# Rev_1.net
KiCad netlist of a schematic drawn in EAGLE
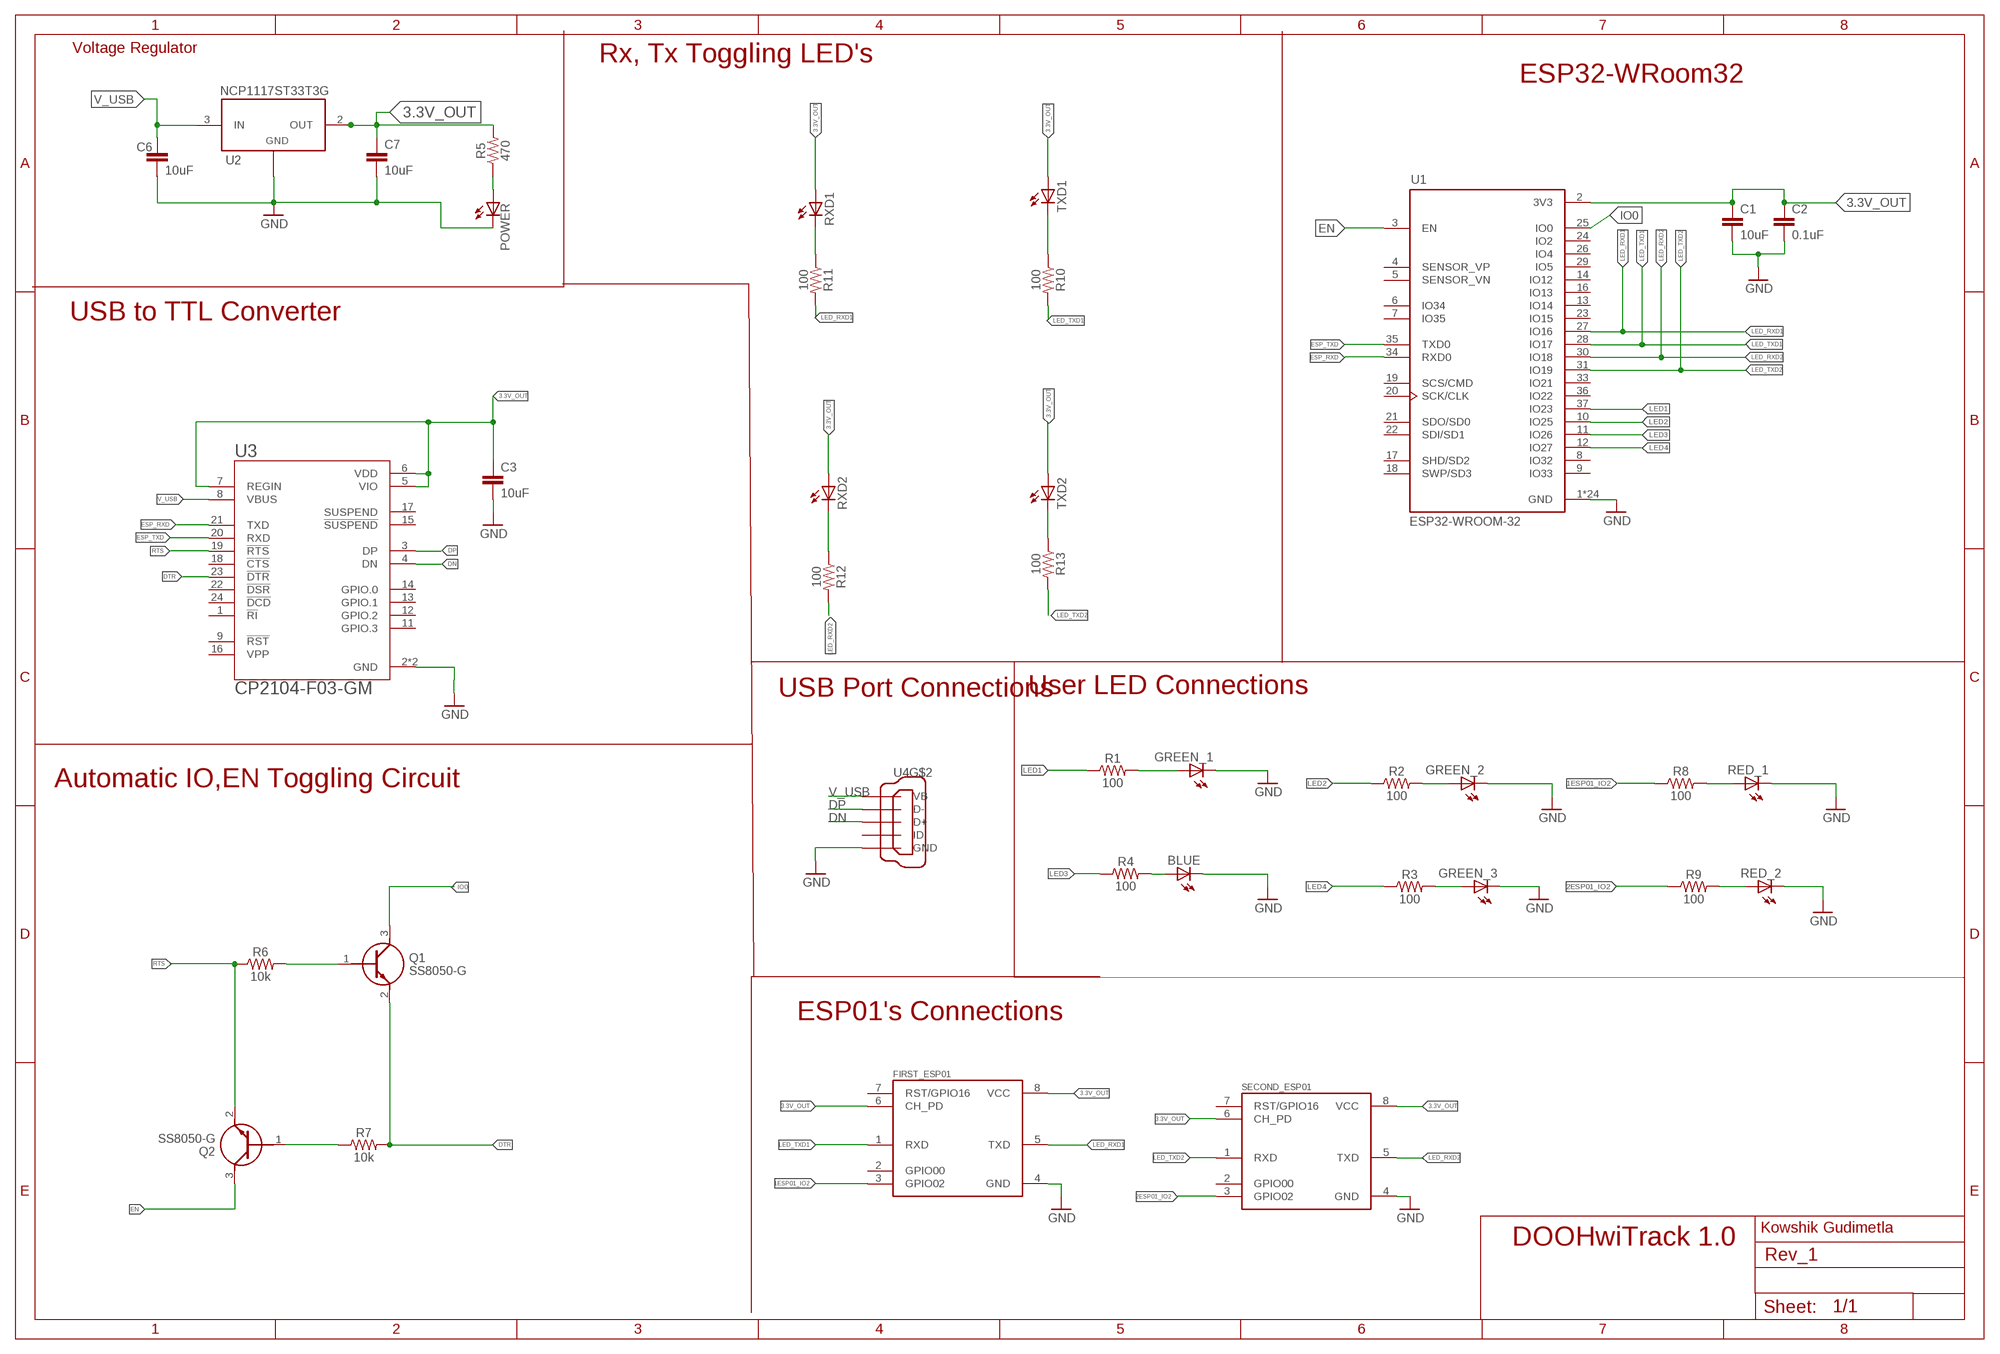
[diagram p0: schematic, sheet 1]

(export (version "E")
  (design (tool "Eeschema 10.0.6"))
  (components
    (comp (ref "BLUE")
      (value "LEDCHIP-LED0805")
      (footprint "eagle-import:CHIP-LED0805")
      (libsource (lib "eagle-import") (part "LEDCHIP-LED0805"))
    )
    (comp (ref "C1")
      (value "10uF")
      (footprint "eagle-import:0402")
      (libsource (lib "eagle-import") (part "0.1UF-0402-16V-10%"))
    )
    (comp (ref "C2")
      (value "0.1uF")
      (footprint "eagle-import:0402")
      (libsource (lib "eagle-import") (part "0.1UF-0402-16V-10%"))
    )
    (comp (ref "C3")
      (value "10uF")
      (footprint "eagle-import:0402")
      (libsource (lib "eagle-import") (part "0.1UF-0402-16V-10%"))
    )
    (comp (ref "C6")
      (value "10uF")
      (footprint "eagle-import:0402")
      (libsource (lib "eagle-import") (part "0.1UF-0402-16V-10%"))
    )
    (comp (ref "C7")
      (value "10uF")
      (footprint "eagle-import:0402")
      (libsource (lib "eagle-import") (part "0.1UF-0402-16V-10%"))
    )
    (comp (ref "FIRST_ESP01")
      (value "ESP8266-01/ESP-01")
      (footprint "eagle-import:XCVR_ESP8266-01_ESP-01")
      (fields (field (name "MF") "AI-Thinker"))
      (libsource (lib "eagle-import") (part "ESP8266-01/ESP-01"))
    )
    (comp (ref "GREEN_1")
      (value "LEDCHIP-LED0805")
      (footprint "eagle-import:CHIP-LED0805")
      (libsource (lib "eagle-import") (part "LEDCHIP-LED0805"))
    )
    (comp (ref "GREEN_2")
      (value "LEDCHIP-LED0805")
      (footprint "eagle-import:CHIP-LED0805")
      (libsource (lib "eagle-import") (part "LEDCHIP-LED0805"))
    )
    (comp (ref "GREEN_3")
      (value "LEDCHIP-LED0805")
      (footprint "eagle-import:CHIP-LED0805")
      (libsource (lib "eagle-import") (part "LEDCHIP-LED0805"))
    )
    (comp (ref "POWER")
      (value "LEDCHIP-LED0603")
      (footprint "eagle-import:CHIP-LED0603")
      (libsource (lib "eagle-import") (part "LEDCHIP-LED0603"))
    )
    (comp (ref "Q1")
      (value "SS8050-G")
      (footprint "eagle-import:SOT95P240X115-3N")
      (fields (field (name "MF") "Comchip Technology"))
      (libsource (lib "eagle-import") (part "SS8050-G"))
    )
    (comp (ref "Q2")
      (value "SS8050-G")
      (footprint "eagle-import:SOT95P240X115-3N")
      (fields (field (name "MF") "Comchip Technology"))
      (libsource (lib "eagle-import") (part "SS8050-G"))
    )
    (comp (ref "R1")
      (value "100")
      (footprint "eagle-import:0402")
      (libsource (lib "eagle-import") (part "100KOHM-0402-1/16W-1%"))
    )
    (comp (ref "R2")
      (value "100")
      (footprint "eagle-import:0402")
      (libsource (lib "eagle-import") (part "100KOHM-0402-1/16W-1%"))
    )
    (comp (ref "R3")
      (value "100")
      (footprint "eagle-import:0402")
      (libsource (lib "eagle-import") (part "100KOHM-0402-1/16W-1%"))
    )
    (comp (ref "R4")
      (value "100")
      (footprint "eagle-import:0402")
      (libsource (lib "eagle-import") (part "100KOHM-0402-1/16W-1%"))
    )
    (comp (ref "R5")
      (value "470")
      (footprint "eagle-import:0402")
      (libsource (lib "eagle-import") (part "100KOHM-0402-1/16W-1%"))
    )
    (comp (ref "R6")
      (value "10k")
      (footprint "eagle-import:0402")
      (libsource (lib "eagle-import") (part "100KOHM-0402-1/16W-1%"))
    )
    (comp (ref "R7")
      (value "10k")
      (footprint "eagle-import:0402")
      (libsource (lib "eagle-import") (part "100KOHM-0402-1/16W-1%"))
    )
    (comp (ref "R8")
      (value "100")
      (footprint "eagle-import:0402")
      (libsource (lib "eagle-import") (part "100KOHM-0402-1/16W-1%"))
    )
    (comp (ref "R9")
      (value "100")
      (footprint "eagle-import:0402")
      (libsource (lib "eagle-import") (part "100KOHM-0402-1/16W-1%"))
    )
    (comp (ref "R10")
      (value "100")
      (footprint "eagle-import:0402")
      (libsource (lib "eagle-import") (part "100KOHM-0402-1/16W-1%"))
    )
    (comp (ref "R11")
      (value "100")
      (footprint "eagle-import:0402")
      (libsource (lib "eagle-import") (part "100KOHM-0402-1/16W-1%"))
    )
    (comp (ref "R12")
      (value "100")
      (footprint "eagle-import:0402")
      (libsource (lib "eagle-import") (part "100KOHM-0402-1/16W-1%"))
    )
    (comp (ref "R13")
      (value "100")
      (footprint "eagle-import:0402")
      (libsource (lib "eagle-import") (part "100KOHM-0402-1/16W-1%"))
    )
    (comp (ref "RED_1")
      (value "LEDCHIP-LED0805")
      (footprint "eagle-import:CHIP-LED0805")
      (libsource (lib "eagle-import") (part "LEDCHIP-LED0805"))
    )
    (comp (ref "RED_2")
      (value "LEDCHIP-LED0805")
      (footprint "eagle-import:CHIP-LED0805")
      (libsource (lib "eagle-import") (part "LEDCHIP-LED0805"))
    )
    (comp (ref "RXD1")
      (value "LEDCHIP-LED0805")
      (footprint "eagle-import:CHIP-LED0805")
      (libsource (lib "eagle-import") (part "LEDCHIP-LED0805"))
    )
    (comp (ref "RXD2")
      (value "LEDCHIP-LED0805")
      (footprint "eagle-import:CHIP-LED0805")
      (libsource (lib "eagle-import") (part "LEDCHIP-LED0805"))
    )
    (comp (ref "SECOND_ESP01")
      (value "ESP8266-01/ESP-01")
      (footprint "eagle-import:XCVR_ESP8266-01_ESP-01")
      (fields (field (name "MF") "AI-Thinker"))
      (libsource (lib "eagle-import") (part "ESP8266-01/ESP-01"))
    )
    (comp (ref "TXD1")
      (value "LEDCHIP-LED0805")
      (footprint "eagle-import:CHIP-LED0805")
      (libsource (lib "eagle-import") (part "LEDCHIP-LED0805"))
    )
    (comp (ref "TXD2")
      (value "LEDCHIP-LED0805")
      (footprint "eagle-import:CHIP-LED0805")
      (libsource (lib "eagle-import") (part "LEDCHIP-LED0805"))
    )
    (comp (ref "U1")
      (value "ESP32-WROOM-32")
      (footprint "eagle-import:MODULE_ESP32-WROOM-32")
      (fields (field (name "MF") "Espressif Systems"))
      (libsource (lib "eagle-import") (part "ESP32-WROOM-32"))
    )
    (comp (ref "U2")
      (value "NCP1117ST33T3G")
      (footprint "eagle-import:SOT-223")
      (fields
        (field (name "DIGIKEY_PART_NUMBER") "NCP1117ST33T3GOSTR-ND")
        (field (name "MANUFACTURER") "ON Semiconductor")
        (field (name "CREATED_BY") "PCBLayout.com")
      )
      (libsource (lib "eagle-import") (part "NCP1117ST33T3G"))
    )
    (comp (ref "U3")
      (value "CP2104-F03-GM")
      (footprint "eagle-import:QFN50P400X400X80-25N")
      (fields (field (name "MF") "Silicon Labs") (field (name "MP") "CP2104"))
      (libsource (lib "eagle-import") (part "CP2104-F03-GM"))
    )
    (comp (ref "U4")
      (value "J_USB_MICROAB_HIROSE_ZX62-AB-5PA")
      (footprint "eagle-import:J_USB_MICROAB_HIROSE_ZX62-AB-5PA")
      (libsource (lib "eagle-import") (part "J_USB_MICROAB_HIROSE_ZX62-AB-5PA"))
    )
  )
  (nets
    (net (code "1") (name "1ESP01_IO2") (class "Default")
      (node (ref "FIRST_ESP01") (pin "3") (pinfunction "GPIO02_3") (pintype "bidirectional"))
      (node (ref "R8") (pin "1") (pinfunction "1_1") (pintype "passive"))
    )
    (net (code "2") (name "2ESP01_IO2") (class "Default")
      (node (ref "R9") (pin "1") (pinfunction "1_1") (pintype "passive"))
      (node (ref "SECOND_ESP01") (pin "3") (pinfunction "GPIO02_3") (pintype "bidirectional"))
    )
    (net (code "3") (name "3.3V_OUT") (class "Default")
      (node (ref "C1") (pin "1") (pinfunction "1_1") (pintype "passive"))
      (node (ref "C2") (pin "1") (pinfunction "1_1") (pintype "passive"))
      (node (ref "C3") (pin "1") (pinfunction "1_1") (pintype "passive"))
      (node (ref "C7") (pin "1") (pinfunction "1_1") (pintype "passive"))
      (node (ref "FIRST_ESP01") (pin "6") (pinfunction "CH_PD_6") (pintype "input"))
      (node (ref "FIRST_ESP01") (pin "8") (pinfunction "VCC_8") (pintype "power_in"))
      (node (ref "R5") (pin "2") (pinfunction "2_2") (pintype "passive"))
      (node (ref "RXD1") (pin "A") (pinfunction "A_A") (pintype "passive"))
      (node (ref "RXD2") (pin "A") (pinfunction "A_A") (pintype "passive"))
      (node (ref "SECOND_ESP01") (pin "6") (pinfunction "CH_PD_6") (pintype "input"))
      (node (ref "SECOND_ESP01") (pin "8") (pinfunction "VCC_8") (pintype "power_in"))
      (node (ref "TXD1") (pin "A") (pinfunction "A_A") (pintype "passive"))
      (node (ref "TXD2") (pin "A") (pinfunction "A_A") (pintype "passive"))
      (node (ref "U1") (pin "2") (pinfunction "3V3_2") (pintype "power_in"))
      (node (ref "U2") (pin "2") (pinfunction "OUT_2") (pintype "output"))
      (node (ref "U2") (pin "4") (pinfunction "4_4") (pintype "passive"))
      (node (ref "U3") (pin "5") (pinfunction "VIO_5") (pintype "power_in"))
      (node (ref "U3") (pin "6") (pinfunction "VDD_6") (pintype "power_in"))
      (node (ref "U3") (pin "7") (pinfunction "REGIN_7") (pintype "input"))
    )
    (net (code "4") (name "DN") (class "Default")
      (node (ref "U3") (pin "4") (pinfunction "DN_4") (pintype "bidirectional"))
      (node (ref "U4") (pin "P$3") (pinfunction "D+_P$3") (pintype "passive"))
    )
    (net (code "5") (name "DP") (class "Default")
      (node (ref "U3") (pin "3") (pinfunction "DP_3") (pintype "bidirectional"))
      (node (ref "U4") (pin "P$2") (pinfunction "D-_P$2") (pintype "passive"))
    )
    (net (code "6") (name "DTR") (class "Default")
      (node (ref "Q1") (pin "2") (pinfunction "E_2") (pintype "bidirectional"))
      (node (ref "R7") (pin "2") (pinfunction "2_2") (pintype "passive"))
      (node (ref "U3") (pin "23") (pinfunction "~{DTR}_23") (pintype "output"))
    )
    (net (code "7") (name "EN") (class "Default")
      (node (ref "Q2") (pin "3") (pinfunction "C_3") (pintype "bidirectional"))
      (node (ref "U1") (pin "3") (pinfunction "EN_3") (pintype "input"))
    )
    (net (code "8") (name "ESP_RXD") (class "Default")
      (node (ref "U1") (pin "34") (pinfunction "RXD0_34") (pintype "bidirectional"))
      (node (ref "U3") (pin "21") (pinfunction "TXD_21") (pintype "output"))
    )
    (net (code "9") (name "ESP_TXD") (class "Default")
      (node (ref "U1") (pin "35") (pinfunction "TXD0_35") (pintype "bidirectional"))
      (node (ref "U3") (pin "20") (pinfunction "RXD_20") (pintype "input"))
    )
    (net (code "10") (name "GND") (class "Default")
      (node (ref "BLUE") (pin "C") (pinfunction "C_C") (pintype "passive"))
      (node (ref "C1") (pin "2") (pinfunction "2_2") (pintype "passive"))
      (node (ref "C2") (pin "2") (pinfunction "2_2") (pintype "passive"))
      (node (ref "C3") (pin "2") (pinfunction "2_2") (pintype "passive"))
      (node (ref "C6") (pin "2") (pinfunction "2_2") (pintype "passive"))
      (node (ref "C7") (pin "2") (pinfunction "2_2") (pintype "passive"))
      (node (ref "FIRST_ESP01") (pin "4") (pinfunction "GND_4") (pintype "power_in"))
      (node (ref "GREEN_1") (pin "C") (pinfunction "C_C") (pintype "passive"))
      (node (ref "GREEN_2") (pin "C") (pinfunction "C_C") (pintype "passive"))
      (node (ref "GREEN_3") (pin "C") (pinfunction "C_C") (pintype "passive"))
      (node (ref "POWER") (pin "C") (pinfunction "C_C") (pintype "passive"))
      (node (ref "RED_1") (pin "C") (pinfunction "C_C") (pintype "passive"))
      (node (ref "RED_2") (pin "C") (pinfunction "C_C") (pintype "passive"))
      (node (ref "SECOND_ESP01") (pin "4") (pinfunction "GND_4") (pintype "power_in"))
      (node (ref "U1") (pin "1") (pinfunction "GND_1") (pintype "power_in"))
      (node (ref "U1") (pin "15") (pinfunction "GND_15") (pintype "power_in"))
      (node (ref "U1") (pin "38") (pinfunction "GND_38") (pintype "power_in"))
      (node (ref "U1") (pin "39_1") (pinfunction "GND_39_1") (pintype "power_in"))
      (node (ref "U1") (pin "39_10") (pinfunction "GND_39_10") (pintype "power_in"))
      (node (ref "U1") (pin "39_11") (pinfunction "GND_39_11") (pintype "power_in"))
      (node (ref "U1") (pin "39_12") (pinfunction "GND_39_12") (pintype "power_in"))
      (node (ref "U1") (pin "39_13") (pinfunction "GND_39_13") (pintype "power_in"))
      (node (ref "U1") (pin "39_14") (pinfunction "GND_39_14") (pintype "power_in"))
      (node (ref "U1") (pin "39_15") (pinfunction "GND_39_15") (pintype "power_in"))
      (node (ref "U1") (pin "39_16") (pinfunction "GND_39_16") (pintype "power_in"))
      (node (ref "U1") (pin "39_17") (pinfunction "GND_39_17") (pintype "power_in"))
      (node (ref "U1") (pin "39_18") (pinfunction "GND_39_18") (pintype "power_in"))
      (node (ref "U1") (pin "39_19") (pinfunction "GND_39_19") (pintype "power_in"))
      (node (ref "U1") (pin "39_2") (pinfunction "GND_39_2") (pintype "power_in"))
      (node (ref "U1") (pin "39_20") (pinfunction "GND_39_20") (pintype "power_in"))
      (node (ref "U1") (pin "39_21") (pinfunction "GND_39_21") (pintype "power_in"))
      (node (ref "U1") (pin "39_3") (pinfunction "GND_39_3") (pintype "power_in"))
      (node (ref "U1") (pin "39_4") (pinfunction "GND_39_4") (pintype "power_in"))
      (node (ref "U1") (pin "39_5") (pinfunction "GND_39_5") (pintype "power_in"))
      (node (ref "U1") (pin "39_6") (pinfunction "GND_39_6") (pintype "power_in"))
      (node (ref "U1") (pin "39_7") (pinfunction "GND_39_7") (pintype "power_in"))
      (node (ref "U1") (pin "39_8") (pinfunction "GND_39_8") (pintype "power_in"))
      (node (ref "U1") (pin "39_9") (pinfunction "GND_39_9") (pintype "power_in"))
      (node (ref "U2") (pin "1") (pinfunction "ADJ/GND_1") (pintype "power_in"))
      (node (ref "U3") (pin "2") (pinfunction "GND_2") (pintype "power_in"))
      (node (ref "U3") (pin "25") (pinfunction "GND_25") (pintype "power_in"))
      (node (ref "U4") (pin "P$5") (pinfunction "GND_P$5") (pintype "passive"))
    )
    (net (code "11") (name "IO0") (class "Default")
      (node (ref "Q1") (pin "3") (pinfunction "C_3") (pintype "bidirectional"))
      (node (ref "U1") (pin "25") (pinfunction "IO0_25") (pintype "bidirectional"))
    )
    (net (code "12") (name "LED1") (class "Default")
      (node (ref "R1") (pin "1") (pinfunction "1_1") (pintype "passive"))
      (node (ref "U1") (pin "37") (pinfunction "IO23_37") (pintype "bidirectional"))
    )
    (net (code "13") (name "LED2") (class "Default")
      (node (ref "R2") (pin "1") (pinfunction "1_1") (pintype "passive"))
      (node (ref "U1") (pin "10") (pinfunction "IO25_10") (pintype "bidirectional"))
    )
    (net (code "14") (name "LED3") (class "Default")
      (node (ref "R4") (pin "1") (pinfunction "1_1") (pintype "passive"))
      (node (ref "U1") (pin "11") (pinfunction "IO26_11") (pintype "bidirectional"))
    )
    (net (code "15") (name "LED4") (class "Default")
      (node (ref "R3") (pin "1") (pinfunction "1_1") (pintype "passive"))
      (node (ref "U1") (pin "12") (pinfunction "IO27_12") (pintype "bidirectional"))
    )
    (net (code "16") (name "LED_RXD1") (class "Default")
      (node (ref "FIRST_ESP01") (pin "5") (pinfunction "TXD_5") (pintype "output"))
      (node (ref "R11") (pin "2") (pinfunction "2_2") (pintype "passive"))
      (node (ref "U1") (pin "27") (pinfunction "IO16_27") (pintype "bidirectional"))
    )
    (net (code "17") (name "LED_RXD2") (class "Default")
      (node (ref "R12") (pin "2") (pinfunction "2_2") (pintype "passive"))
      (node (ref "SECOND_ESP01") (pin "5") (pinfunction "TXD_5") (pintype "output"))
      (node (ref "U1") (pin "30") (pinfunction "IO18_30") (pintype "bidirectional"))
    )
    (net (code "18") (name "LED_TXD1") (class "Default")
      (node (ref "FIRST_ESP01") (pin "1") (pinfunction "RXD_1") (pintype "input"))
      (node (ref "R10") (pin "2") (pinfunction "2_2") (pintype "passive"))
      (node (ref "U1") (pin "28") (pinfunction "IO17_28") (pintype "bidirectional"))
    )
    (net (code "19") (name "LED_TXD2") (class "Default")
      (node (ref "R13") (pin "2") (pinfunction "2_2") (pintype "passive"))
      (node (ref "SECOND_ESP01") (pin "1") (pinfunction "RXD_1") (pintype "input"))
      (node (ref "U1") (pin "31") (pinfunction "IO19_31") (pintype "bidirectional"))
    )
    (net (code "20") (name "Net-(BLUE-PadA)") (class "Default")
      (node (ref "BLUE") (pin "A") (pinfunction "A_A") (pintype "passive"))
      (node (ref "R4") (pin "2") (pinfunction "2_2") (pintype "passive"))
    )
    (net (code "21") (name "Net-(GREEN_1-PadA)") (class "Default")
      (node (ref "GREEN_1") (pin "A") (pinfunction "A_A") (pintype "passive"))
      (node (ref "R1") (pin "2") (pinfunction "2_2") (pintype "passive"))
    )
    (net (code "22") (name "Net-(GREEN_2-PadA)") (class "Default")
      (node (ref "GREEN_2") (pin "A") (pinfunction "A_A") (pintype "passive"))
      (node (ref "R2") (pin "2") (pinfunction "2_2") (pintype "passive"))
    )
    (net (code "23") (name "Net-(GREEN_3-PadA)") (class "Default")
      (node (ref "GREEN_3") (pin "A") (pinfunction "A_A") (pintype "passive"))
      (node (ref "R3") (pin "2") (pinfunction "2_2") (pintype "passive"))
    )
    (net (code "24") (name "Net-(POWER-PadA)") (class "Default")
      (node (ref "POWER") (pin "A") (pinfunction "A_A") (pintype "passive"))
      (node (ref "R5") (pin "1") (pinfunction "1_1") (pintype "passive"))
    )
    (net (code "25") (name "Net-(Q1-B)") (class "Default")
      (node (ref "Q1") (pin "1") (pinfunction "B_1") (pintype "bidirectional"))
      (node (ref "R6") (pin "2") (pinfunction "2_2") (pintype "passive"))
    )
    (net (code "26") (name "Net-(Q2-B)") (class "Default")
      (node (ref "Q2") (pin "1") (pinfunction "B_1") (pintype "bidirectional"))
      (node (ref "R7") (pin "1") (pinfunction "1_1") (pintype "passive"))
    )
    (net (code "27") (name "Net-(R8-Pad2)") (class "Default")
      (node (ref "R8") (pin "2") (pinfunction "2_2") (pintype "passive"))
      (node (ref "RED_1") (pin "A") (pinfunction "A_A") (pintype "passive"))
    )
    (net (code "28") (name "Net-(R9-Pad2)") (class "Default")
      (node (ref "R9") (pin "2") (pinfunction "2_2") (pintype "passive"))
      (node (ref "RED_2") (pin "A") (pinfunction "A_A") (pintype "passive"))
    )
    (net (code "29") (name "Net-(R10-Pad1)") (class "Default")
      (node (ref "R10") (pin "1") (pinfunction "1_1") (pintype "passive"))
      (node (ref "TXD1") (pin "C") (pinfunction "C_C") (pintype "passive"))
    )
    (net (code "30") (name "Net-(R11-Pad1)") (class "Default")
      (node (ref "R11") (pin "1") (pinfunction "1_1") (pintype "passive"))
      (node (ref "RXD1") (pin "C") (pinfunction "C_C") (pintype "passive"))
    )
    (net (code "31") (name "Net-(R12-Pad1)") (class "Default")
      (node (ref "R12") (pin "1") (pinfunction "1_1") (pintype "passive"))
      (node (ref "RXD2") (pin "C") (pinfunction "C_C") (pintype "passive"))
    )
    (net (code "32") (name "Net-(R13-Pad1)") (class "Default")
      (node (ref "R13") (pin "1") (pinfunction "1_1") (pintype "passive"))
      (node (ref "TXD2") (pin "C") (pinfunction "C_C") (pintype "passive"))
    )
    (net (code "33") (name "RTS") (class "Default")
      (node (ref "Q2") (pin "2") (pinfunction "E_2") (pintype "bidirectional"))
      (node (ref "R6") (pin "1") (pinfunction "1_1") (pintype "passive"))
      (node (ref "U3") (pin "19") (pinfunction "~{RTS}_19") (pintype "output"))
    )
    (net (code "34") (name "V_USB") (class "Default")
      (node (ref "C6") (pin "1") (pinfunction "1_1") (pintype "passive"))
      (node (ref "U2") (pin "3") (pinfunction "IN_3") (pintype "input"))
      (node (ref "U3") (pin "8") (pinfunction "VBUS_8") (pintype "input"))
      (node (ref "U4") (pin "P$1") (pinfunction "VB_P$1") (pintype "passive"))
    )
    (net (code "35") (name "unconnected-(FIRST_ESP01-GPIO00-Pad2)") (class "Default")
      (node (ref "FIRST_ESP01") (pin "2") (pinfunction "GPIO00_2") (pintype "bidirectional"))
    )
    (net (code "36") (name "unconnected-(FIRST_ESP01-RST{slash}GPIO16-Pad7)") (class "Default")
      (node (ref "FIRST_ESP01") (pin "7") (pinfunction "RST/GPIO16_7") (pintype "input"))
    )
    (net (code "37") (name "unconnected-(SECOND_ESP01-GPIO00-Pad2)") (class "Default")
      (node (ref "SECOND_ESP01") (pin "2") (pinfunction "GPIO00_2") (pintype "bidirectional"))
    )
    (net (code "38") (name "unconnected-(SECOND_ESP01-RST{slash}GPIO16-Pad7)") (class "Default")
      (node (ref "SECOND_ESP01") (pin "7") (pinfunction "RST/GPIO16_7") (pintype "input"))
    )
    (net (code "39") (name "unconnected-(U1-IO2-Pad24)") (class "Default")
      (node (ref "U1") (pin "24") (pinfunction "IO2_24") (pintype "bidirectional"))
    )
    (net (code "40") (name "unconnected-(U1-IO4-Pad26)") (class "Default")
      (node (ref "U1") (pin "26") (pinfunction "IO4_26") (pintype "bidirectional"))
    )
    (net (code "41") (name "unconnected-(U1-IO5-Pad29)") (class "Default")
      (node (ref "U1") (pin "29") (pinfunction "IO5_29") (pintype "bidirectional"))
    )
    (net (code "42") (name "unconnected-(U1-IO12-Pad14)") (class "Default")
      (node (ref "U1") (pin "14") (pinfunction "IO12_14") (pintype "bidirectional"))
    )
    (net (code "43") (name "unconnected-(U1-IO13-Pad16)") (class "Default")
      (node (ref "U1") (pin "16") (pinfunction "IO13_16") (pintype "bidirectional"))
    )
    (net (code "44") (name "unconnected-(U1-IO14-Pad13)") (class "Default")
      (node (ref "U1") (pin "13") (pinfunction "IO14_13") (pintype "bidirectional"))
    )
    (net (code "45") (name "unconnected-(U1-IO15-Pad23)") (class "Default")
      (node (ref "U1") (pin "23") (pinfunction "IO15_23") (pintype "bidirectional"))
    )
    (net (code "46") (name "unconnected-(U1-IO21-Pad33)") (class "Default")
      (node (ref "U1") (pin "33") (pinfunction "IO21_33") (pintype "bidirectional"))
    )
    (net (code "47") (name "unconnected-(U1-IO22-Pad36)") (class "Default")
      (node (ref "U1") (pin "36") (pinfunction "IO22_36") (pintype "bidirectional"))
    )
    (net (code "48") (name "unconnected-(U1-IO32-Pad8)") (class "Default")
      (node (ref "U1") (pin "8") (pinfunction "IO32_8") (pintype "bidirectional"))
    )
    (net (code "49") (name "unconnected-(U1-IO33-Pad9)") (class "Default")
      (node (ref "U1") (pin "9") (pinfunction "IO33_9") (pintype "bidirectional"))
    )
    (net (code "50") (name "unconnected-(U1-IO34-Pad6)") (class "Default")
      (node (ref "U1") (pin "6") (pinfunction "IO34_6") (pintype "input"))
    )
    (net (code "51") (name "unconnected-(U1-IO35-Pad7)") (class "Default")
      (node (ref "U1") (pin "7") (pinfunction "IO35_7") (pintype "input"))
    )
    (net (code "52") (name "unconnected-(U1-SCK{slash}CLK-Pad20)") (class "Default")
      (node (ref "U1") (pin "20") (pinfunction "SCK/CLK_20") (pintype "bidirectional"))
    )
    (net (code "53") (name "unconnected-(U1-SCS{slash}CMD-Pad19)") (class "Default")
      (node (ref "U1") (pin "19") (pinfunction "SCS/CMD_19") (pintype "bidirectional"))
    )
    (net (code "54") (name "unconnected-(U1-SDI{slash}SD1-Pad22)") (class "Default")
      (node (ref "U1") (pin "22") (pinfunction "SDI/SD1_22") (pintype "bidirectional"))
    )
    (net (code "55") (name "unconnected-(U1-SDO{slash}SD0-Pad21)") (class "Default")
      (node (ref "U1") (pin "21") (pinfunction "SDO/SD0_21") (pintype "bidirectional"))
    )
    (net (code "56") (name "unconnected-(U1-SENSOR_VN-Pad5)") (class "Default")
      (node (ref "U1") (pin "5") (pinfunction "SENSOR_VN_5") (pintype "input"))
    )
    (net (code "57") (name "unconnected-(U1-SENSOR_VP-Pad4)") (class "Default")
      (node (ref "U1") (pin "4") (pinfunction "SENSOR_VP_4") (pintype "input"))
    )
    (net (code "58") (name "unconnected-(U1-SHD{slash}SD2-Pad17)") (class "Default")
      (node (ref "U1") (pin "17") (pinfunction "SHD/SD2_17") (pintype "bidirectional"))
    )
    (net (code "59") (name "unconnected-(U1-SWP{slash}SD3-Pad18)") (class "Default")
      (node (ref "U1") (pin "18") (pinfunction "SWP/SD3_18") (pintype "bidirectional"))
    )
    (net (code "60") (name "unconnected-(U3-GPIO.0-Pad14)") (class "Default")
      (node (ref "U3") (pin "14") (pinfunction "GPIO.0_14") (pintype "bidirectional"))
    )
    (net (code "61") (name "unconnected-(U3-GPIO.1-Pad13)") (class "Default")
      (node (ref "U3") (pin "13") (pinfunction "GPIO.1_13") (pintype "bidirectional"))
    )
    (net (code "62") (name "unconnected-(U3-GPIO.2-Pad12)") (class "Default")
      (node (ref "U3") (pin "12") (pinfunction "GPIO.2_12") (pintype "bidirectional"))
    )
    (net (code "63") (name "unconnected-(U3-GPIO.3-Pad11)") (class "Default")
      (node (ref "U3") (pin "11") (pinfunction "GPIO.3_11") (pintype "bidirectional"))
    )
    (net (code "64") (name "unconnected-(U3-SUSPEND-Pad17)") (class "Default")
      (node (ref "U3") (pin "17") (pinfunction "SUSPEND_17") (pintype "output"))
    )
    (net (code "65") (name "unconnected-(U3-VPP-Pad16)") (class "Default")
      (node (ref "U3") (pin "16") (pinfunction "VPP_16") (pintype "passive"))
    )
    (net (code "66") (name "unconnected-(U3-~{CTS}-Pad18)") (class "Default")
      (node (ref "U3") (pin "18") (pinfunction "~{CTS}_18") (pintype "input"))
    )
    (net (code "67") (name "unconnected-(U3-~{DCD}-Pad24)") (class "Default")
      (node (ref "U3") (pin "24") (pinfunction "~{DCD}_24") (pintype "input"))
    )
    (net (code "68") (name "unconnected-(U3-~{DSR}-Pad22)") (class "Default")
      (node (ref "U3") (pin "22") (pinfunction "~{DSR}_22") (pintype "input"))
    )
    (net (code "69") (name "unconnected-(U3-~{RI}-Pad1)") (class "Default")
      (node (ref "U3") (pin "1") (pinfunction "~{RI}_1") (pintype "input"))
    )
    (net (code "70") (name "unconnected-(U3-~{RST}-Pad9)") (class "Default")
      (node (ref "U3") (pin "9") (pinfunction "~{RST}_9") (pintype "bidirectional"))
    )
    (net (code "71") (name "unconnected-(U3-~{SUSPEND}-Pad15)") (class "Default")
      (node (ref "U3") (pin "15") (pinfunction "~{SUSPEND}_15") (pintype "output"))
    )
    (net (code "72") (name "unconnected-(U4B-ID-PadP$4)") (class "Default")
      (node (ref "U4") (pin "P$4") (pinfunction "ID_P$4") (pintype "passive"))
    )
  )
)
